# MAX_M10S.net
KiCad netlist of a schematic drawn in Altium Designer
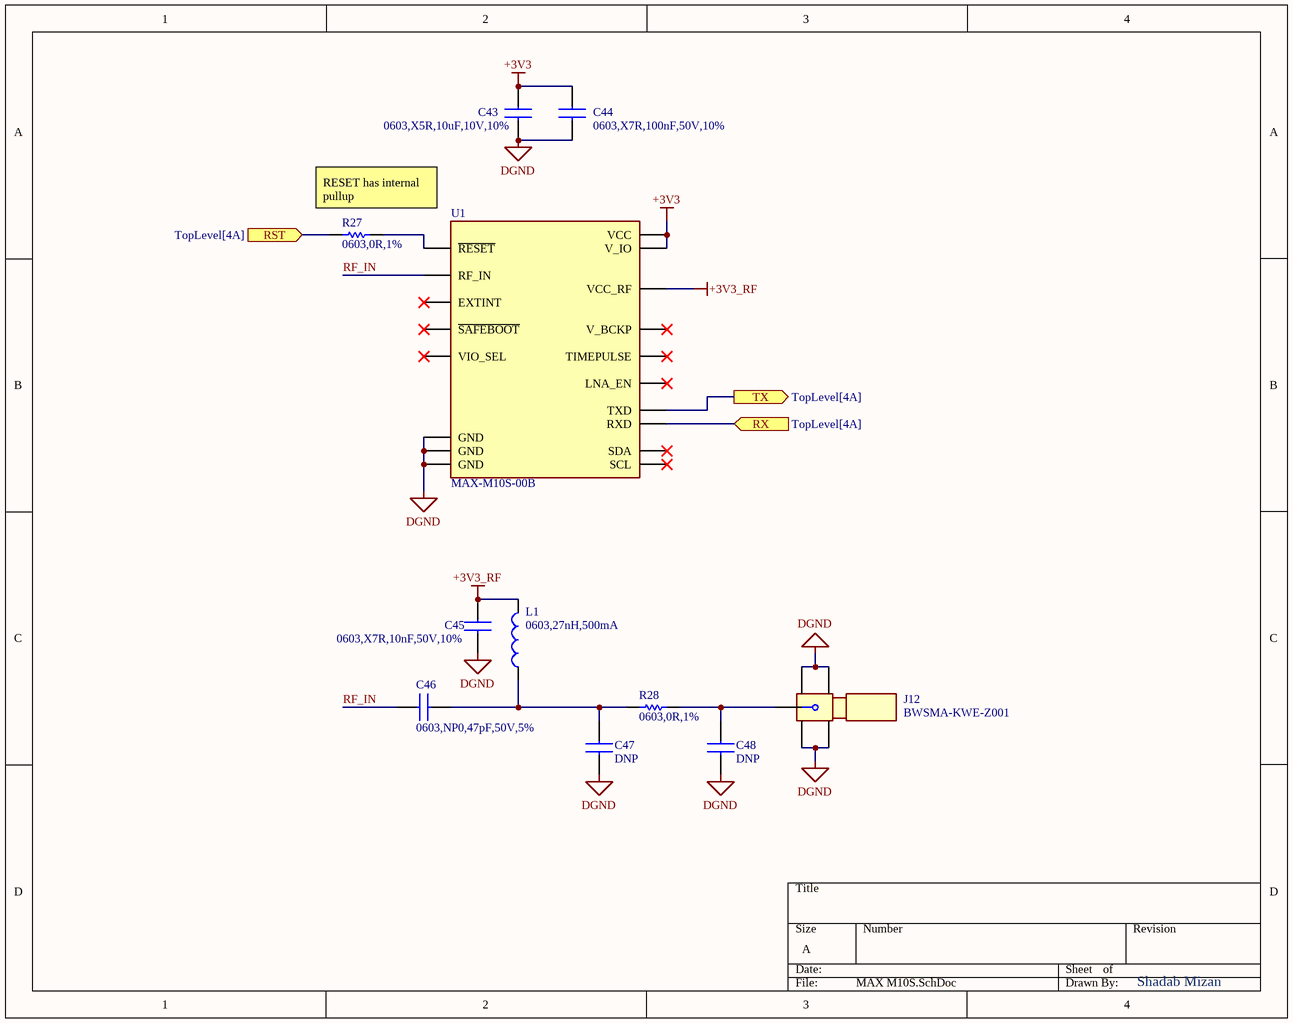
[diagram p0: MAX M10S.SchDoc]

(export (version "E")
  (design (tool "Eeschema 10.0.6"))
  (components
    (comp (ref "C43")
      (value "0603,X5R,10uF,10V,10%")
      (footprint "CAPC1608X90N")
      (description "10uF ±10% 10V Ceramic Capacitor X5R 0603")
      (fields (field (name "LCSC PART #") "C19702") (field (name "MANU PART #") "CL10A106KP8NNNC"))
      (libsource (lib "flight-controller") (part "CL10A106KP8NNNC"))
    )
    (comp (ref "C44")
      (value "0603,X7R,100nF,50V,10%")
      (footprint "CAPC1608X90N")
      (description "50V 100nF X7R ±10% 0603 Multilayer Ceramic Capacitors MLCC - SMD/SMT ROHS")
      (fields (field (name "LCSC PART #") "C14663") (field (name "MANU PART #") "CC0603KRX7R9BB104"))
      (libsource (lib "flight-controller") (part "CC0603KRX7R9BB104"))
    )
    (comp (ref "C45")
      (value "0603,X7R,10nF,50V,10%")
      (footprint "CAPC1608X90N")
      (description "10nF ±10% 50V Ceramic Capacitor X7R 0603")
      (fields (field (name "LCSC PART #") "C57112") (field (name "MANU PART #") "0603B103K500NT"))
      (libsource (lib "flight-controller") (part "0603B103K500NT"))
    )
    (comp (ref "C46")
      (value "0603,NP0,47pF,50V,5%")
      (footprint "CAPC1608X90N")
      (description "47 pF ±5% 50V Ceramic Capacitor C0G, NP0 0603 (1608 Metric)")
      (fields (field (name "MANU PART #") "CL10C470JB8NNNC") (field (name "LCSC PART #") "C1671"))
      (libsource (lib "flight-controller") (part "CL10C470JB8NNNC"))
    )
    (comp (ref "C47")
      (value "DNP")
      (footprint "CAPC1608X90N")
      (description "10nF ±10% 50V Ceramic Capacitor X7R 0603")
      (fields (field (name "LCSC PART #") "C100042") (field (name "MANU PART #") "CC0603KRX7R9BB103"))
      (libsource (lib "flight-controller") (part "CC0603KRX7R9BB103"))
    )
    (comp (ref "C48")
      (value "DNP")
      (footprint "CAPC1608X90N")
      (description "10nF ±10% 50V Ceramic Capacitor X7R 0603")
      (fields (field (name "LCSC PART #") "C100042") (field (name "MANU PART #") "CC0603KRX7R9BB103"))
      (libsource (lib "flight-controller") (part "CC0603KRX7R9BB103"))
    )
    (comp (ref "J12")
      (value "BWSMA-KWE-Z001")
      (footprint "SMA-TH_BWSMA-KWE-Z001")
      (description "Connector Receptacle SMA Female Pin 50Ω Through Hole Right Angle")
      (fields (field (name "LCSC PART #") "C496551"))
      (libsource (lib "flight-controller") (part "BWSMA-KWE-Z001"))
    )
    (comp (ref "L1")
      (value "0603,27nH,500mA")
      (footprint "INDC1608X90N")
      (description "27 nH Unshielded Multilayer Inductor 500 mA 550mOhm Max 0603 (1608 Metric)")
      (fields (field (name "MANU PART #") "LQG18HN27NJ00D") (field (name "LCSC PART #") "C162550"))
      (libsource (lib "flight-controller") (part "LQG18HN27NJ00D"))
    )
    (comp (ref "R27")
      (value "0603,0R,1%")
      (footprint "RESC1608X90N")
      (description "0Ω 100mW 75V Thick Film Resistor ±1% 0603 Chip Resistor - Surface Mount RoHS")
      (fields (field (name "LCSC PART #") "C21189") (field (name "MANU PART #") "0603WAF0000T5E"))
      (libsource (lib "flight-controller") (part "0603WAF0000T5E"))
    )
    (comp (ref "R28")
      (value "0603,0R,1%")
      (footprint "RESC1608X90N")
      (description "0Ω 100mW 75V Thick Film Resistor ±1% 0603 Chip Resistor - Surface Mount RoHS")
      (fields (field (name "LCSC PART #") "C21189") (field (name "MANU PART #") "0603WAF0000T5E"))
      (libsource (lib "flight-controller") (part "0603WAF0000T5E"))
    )
    (comp (ref "U1")
      (value "MAX-M10S-00B")
      (footprint "XCVR_MAX-M10S-00B")
      (description "Standard precision GNSS module")
      (fields (field (name "LCSC PART #") "C4153167"))
      (libsource (lib "flight-controller") (part "MAX-M10S-00B"))
    )
  )
  (nets
    (net (code "1") (name "+3V3") (class "Default")
      (node (ref "C43") (pin "2") (pinfunction "2_2") (pintype "passive"))
      (node (ref "C44") (pin "2") (pinfunction "2_2") (pintype "passive"))
      (node (ref "U1") (pin "7") (pinfunction "V_IO_7") (pintype "passive"))
      (node (ref "U1") (pin "8") (pinfunction "VCC_8") (pintype "passive"))
    )
    (net (code "2") (name "+3V3_RF") (class "Default")
      (node (ref "C45") (pin "2") (pinfunction "2_2") (pintype "passive"))
      (node (ref "L1") (pin "2") (pinfunction "2_2") (pintype "passive"))
      (node (ref "U1") (pin "14") (pinfunction "VCC_RF_14") (pintype "passive"))
    )
    (net (code "3") (name "/RF_IN") (class "Default")
      (node (ref "C46") (pin "1") (pinfunction "1_1") (pintype "passive"))
      (node (ref "U1") (pin "11") (pinfunction "RF_IN_11") (pintype "passive"))
    )
    (net (code "4") (name "/RST") (class "Default")
      (node (ref "R27") (pin "1") (pinfunction "1_1") (pintype "passive"))
    )
    (net (code "5") (name "/RX") (class "Default")
      (node (ref "U1") (pin "3") (pinfunction "RXD_3") (pintype "passive"))
    )
    (net (code "6") (name "/TX") (class "Default")
      (node (ref "U1") (pin "2") (pinfunction "TXD_2") (pintype "passive"))
    )
    (net (code "7") (name "DGND") (class "Default")
      (node (ref "C43") (pin "1") (pinfunction "1_1") (pintype "passive"))
      (node (ref "C44") (pin "1") (pinfunction "1_1") (pintype "passive"))
      (node (ref "C45") (pin "1") (pinfunction "1_1") (pintype "passive"))
      (node (ref "C47") (pin "1") (pinfunction "1_1") (pintype "passive"))
      (node (ref "C48") (pin "1") (pinfunction "1_1") (pintype "passive"))
      (node (ref "J12") (pin "1") (pinfunction "1_1") (pintype "passive"))
      (node (ref "J12") (pin "2") (pinfunction "2_2") (pintype "passive"))
      (node (ref "J12") (pin "3") (pinfunction "3_3") (pintype "passive"))
      (node (ref "J12") (pin "4") (pinfunction "4_4") (pintype "passive"))
      (node (ref "U1") (pin "1") (pinfunction "GND_1") (pintype "passive"))
      (node (ref "U1") (pin "10") (pinfunction "GND_10") (pintype "passive"))
      (node (ref "U1") (pin "12") (pinfunction "GND_12") (pintype "passive"))
    )
    (net (code "8") (name "Net-(C46-Pad2)") (class "Default")
      (node (ref "C46") (pin "2") (pinfunction "2_2") (pintype "passive"))
      (node (ref "C47") (pin "2") (pinfunction "2_2") (pintype "passive"))
      (node (ref "L1") (pin "1") (pinfunction "1_1") (pintype "passive"))
      (node (ref "R28") (pin "1") (pinfunction "1_1") (pintype "passive"))
    )
    (net (code "9") (name "Net-(C48-Pad2)") (class "Default")
      (node (ref "C48") (pin "2") (pinfunction "2_2") (pintype "passive"))
      (node (ref "J12") (pin "5") (pinfunction "5_5") (pintype "passive"))
      (node (ref "R28") (pin "2") (pinfunction "2_2") (pintype "passive"))
    )
    (net (code "10") (name "Net-(U1-~{RESET})") (class "Default")
      (node (ref "R27") (pin "2") (pinfunction "2_2") (pintype "passive"))
      (node (ref "U1") (pin "9") (pinfunction "~{RESET}_9") (pintype "passive"))
    )
    (net (code "11") (name "unconnected-(U1-EXTINT-Pad5)") (class "Default")
      (node (ref "U1") (pin "5") (pinfunction "EXTINT_5") (pintype "passive+no_connect"))
    )
    (net (code "12") (name "unconnected-(U1-LNA_EN-Pad13)") (class "Default")
      (node (ref "U1") (pin "13") (pinfunction "LNA_EN_13") (pintype "passive+no_connect"))
    )
    (net (code "13") (name "unconnected-(U1-SCL-Pad17)") (class "Default")
      (node (ref "U1") (pin "17") (pinfunction "SCL_17") (pintype "passive+no_connect"))
    )
    (net (code "14") (name "unconnected-(U1-SDA-Pad16)") (class "Default")
      (node (ref "U1") (pin "16") (pinfunction "SDA_16") (pintype "passive+no_connect"))
    )
    (net (code "15") (name "unconnected-(U1-TIMEPULSE-Pad4)") (class "Default")
      (node (ref "U1") (pin "4") (pinfunction "TIMEPULSE_4") (pintype "passive+no_connect"))
    )
    (net (code "16") (name "unconnected-(U1-VIO_SEL-Pad15)") (class "Default")
      (node (ref "U1") (pin "15") (pinfunction "VIO_SEL_15") (pintype "passive+no_connect"))
    )
    (net (code "17") (name "unconnected-(U1-V_BCKP-Pad6)") (class "Default")
      (node (ref "U1") (pin "6") (pinfunction "V_BCKP_6") (pintype "passive+no_connect"))
    )
    (net (code "18") (name "unconnected-(U1-~{SAFEBOOT}-Pad18)") (class "Default")
      (node (ref "U1") (pin "18") (pinfunction "~{SAFEBOOT}_18") (pintype "passive+no_connect"))
    )
  )
)
